# Main_Board_-_Double__Discrete.net
KiCad netlist of a schematic drawn in EAGLE
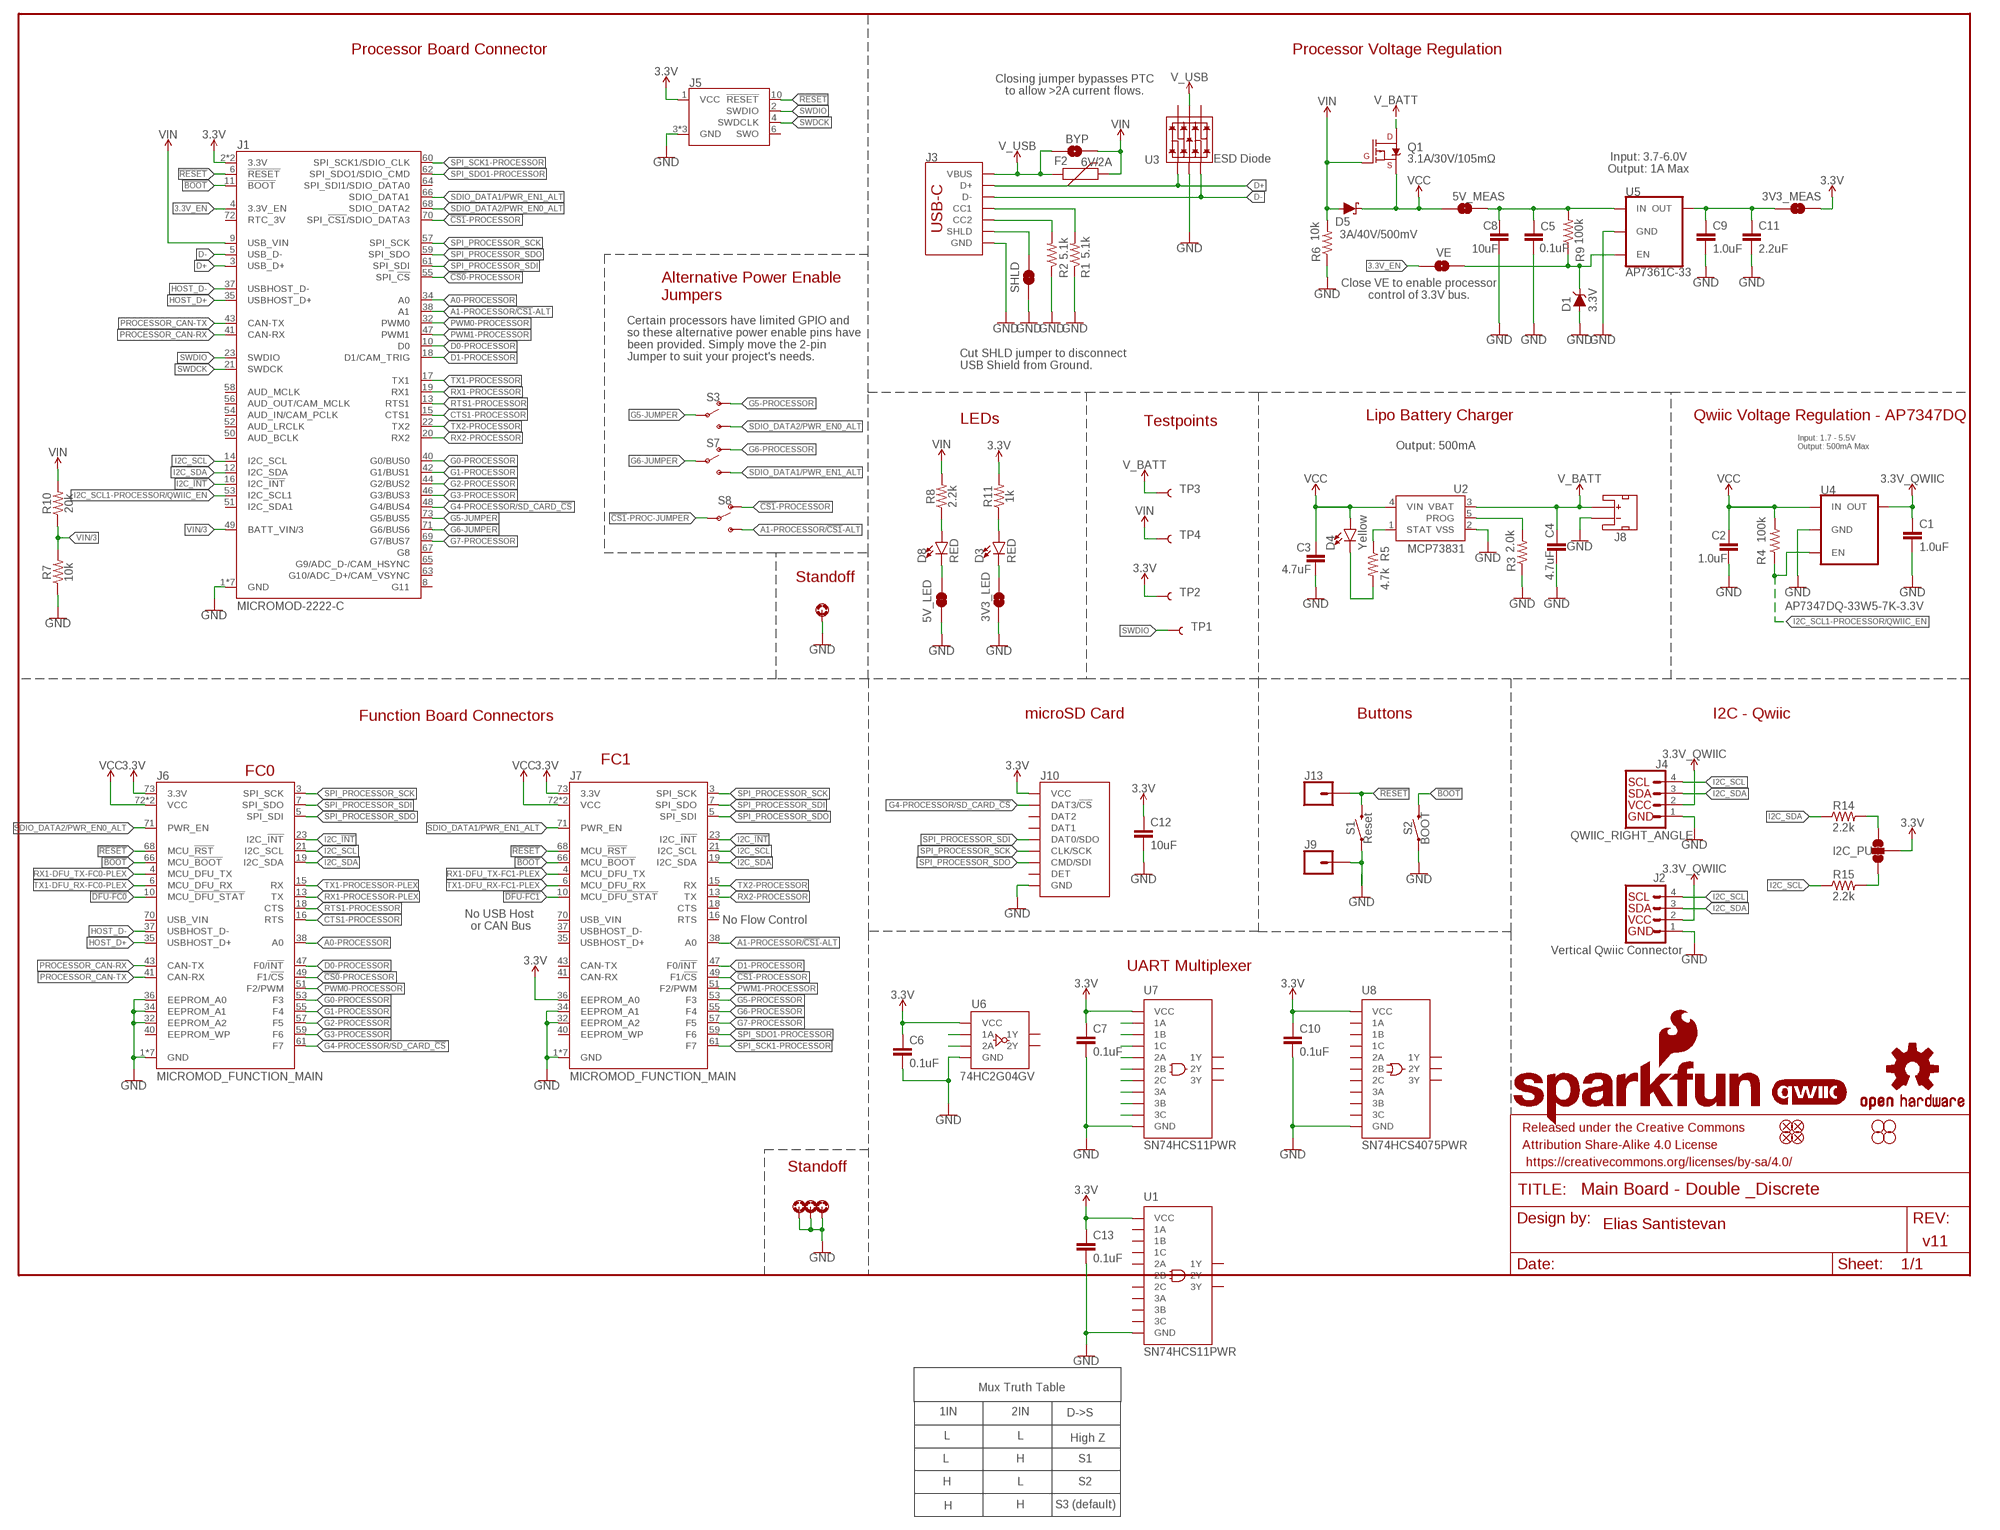
[diagram p0: schematic, sheet 1]

(export (version "E")
  (design (tool "Eeschema 10.0.6"))
  (components
    (comp (ref "3V3_LED")
      (value "JUMPER-SMT_2_NC_TRACE_SILK")
      (footprint "eagle-import:SMT-JUMPER_2_NC_TRACE_SILK")
      (libsource (lib "eagle-import") (part "JUMPER-SMT_2_NC_TRACE_SILK"))
    )
    (comp (ref "3V3_MEAS")
      (value "JUMPER-COMBO_2_NC_TRACE")
      (footprint "eagle-import:COMBO-JUMPER_2_NC_TRACE")
      (libsource (lib "eagle-import") (part "JUMPER-COMBO_2_NC_TRACE"))
    )
    (comp (ref "5V_LED")
      (value "JUMPER-SMT_2_NC_TRACE_SILK")
      (footprint "eagle-import:SMT-JUMPER_2_NC_TRACE_SILK")
      (libsource (lib "eagle-import") (part "JUMPER-SMT_2_NC_TRACE_SILK"))
    )
    (comp (ref "5V_MEAS")
      (value "JUMPER-COMBO_2_NC_TRACE")
      (footprint "eagle-import:COMBO-JUMPER_2_NC_TRACE")
      (libsource (lib "eagle-import") (part "JUMPER-COMBO_2_NC_TRACE"))
    )
    (comp (ref "BYP")
      (value "JUMPER-SMT_2_NO_SILK")
      (footprint "eagle-import:SMT-JUMPER_2_NO_SILK")
      (libsource (lib "eagle-import") (part "JUMPER-SMT_2_NO_SILK"))
    )
    (comp (ref "C1")
      (value "1.0uF")
      (footprint "eagle-import:0603")
      (libsource (lib "eagle-import") (part "1.0UF-0603-16V-10%"))
    )
    (comp (ref "C2")
      (value "1.0uF")
      (footprint "eagle-import:0603")
      (libsource (lib "eagle-import") (part "1.0UF-0603-16V-10%"))
    )
    (comp (ref "C3")
      (value "4.7uF")
      (footprint "eagle-import:0603")
      (libsource (lib "eagle-import") (part "4.7UF-0603-6.3V-(10%)"))
    )
    (comp (ref "C4")
      (value "4.7uF")
      (footprint "eagle-import:0603")
      (libsource (lib "eagle-import") (part "4.7UF-0603-35V-(20%)"))
    )
    (comp (ref "C5")
      (value "0.1uF")
      (footprint "eagle-import:0603")
      (libsource (lib "eagle-import") (part "0.1UF-0603-25V-(+80/-20%)"))
    )
    (comp (ref "C6")
      (value "0.1uF")
      (footprint "eagle-import:0603")
      (libsource (lib "eagle-import") (part "0.1UF-0603-25V-(+80/-20%)"))
    )
    (comp (ref "C7")
      (value "0.1uF")
      (footprint "eagle-import:0603")
      (libsource (lib "eagle-import") (part "0.1UF-0603-25V-(+80/-20%)"))
    )
    (comp (ref "C8")
      (value "10uF")
      (footprint "eagle-import:0805")
      (libsource (lib "eagle-import") (part "10UF-0805-10V-10%"))
    )
    (comp (ref "C9")
      (value "1.0uF")
      (footprint "eagle-import:0603")
      (libsource (lib "eagle-import") (part "1.0UF-0603-16V-10%"))
    )
    (comp (ref "C10")
      (value "0.1uF")
      (footprint "eagle-import:0603")
      (libsource (lib "eagle-import") (part "0.1UF-0603-25V-(+80/-20%)"))
    )
    (comp (ref "C11")
      (value "2.2uF")
      (footprint "eagle-import:0603")
      (libsource (lib "eagle-import") (part "2.2UF-0603-10V-20%"))
    )
    (comp (ref "C12")
      (value "10uF")
      (footprint "eagle-import:0603")
      (libsource (lib "eagle-import") (part "10UF-0603-6.3V-20%"))
    )
    (comp (ref "C13")
      (value "0.1uF")
      (footprint "eagle-import:0603")
      (libsource (lib "eagle-import") (part "0.1UF-0603-25V-(+80/-20%)"))
    )
    (comp (ref "D1")
      (value "3.3V")
      (footprint "eagle-import:SOD-323")
      (libsource (lib "eagle-import") (part "DIODE-ZENER-MM3Z3V3T1G"))
    )
    (comp (ref "D3")
      (value "RED")
      (footprint "eagle-import:LED-0603")
      (libsource (lib "eagle-import") (part "LED-RED0603"))
    )
    (comp (ref "D4")
      (value "Yellow")
      (footprint "eagle-import:LED-0603")
      (libsource (lib "eagle-import") (part "LED-YELLOW0603"))
    )
    (comp (ref "D5")
      (value "3A/40V/500mV")
      (footprint "eagle-import:SMA-DIODE")
      (libsource (lib "eagle-import") (part "DIODE-SCHOTTKY-B340A"))
    )
    (comp (ref "D8")
      (value "RED")
      (footprint "eagle-import:LED-0603")
      (libsource (lib "eagle-import") (part "LED-RED0603"))
    )
    (comp (ref "F2")
      (value "6V/2A")
      (footprint "eagle-import:1210")
      (libsource (lib "eagle-import") (part "PPTC_6V2A"))
    )
    (comp (ref "FD1")
      (value "FIDUCIAL1X2")
      (footprint "eagle-import:FIDUCIAL-1X2")
      (libsource (lib "eagle-import") (part "FIDUCIAL1X2"))
    )
    (comp (ref "FD2")
      (value "FIDUCIAL1X2")
      (footprint "eagle-import:FIDUCIAL-1X2")
      (libsource (lib "eagle-import") (part "FIDUCIAL1X2"))
    )
    (comp (ref "FD3")
      (value "FIDUCIAL1X2")
      (footprint "eagle-import:FIDUCIAL-1X2")
      (libsource (lib "eagle-import") (part "FIDUCIAL1X2"))
    )
    (comp (ref "FD4")
      (value "FIDUCIAL1X2")
      (footprint "eagle-import:FIDUCIAL-1X2")
      (libsource (lib "eagle-import") (part "FIDUCIAL1X2"))
    )
    (comp (ref "FRAME1")
      (value "FRAME-LEDGER")
      (footprint "eagle-import:CREATIVE_COMMONS")
      (libsource (lib "eagle-import") (part "FRAME-LEDGER"))
    )
    (comp (ref "H2")
      (value "STAND-OFF-REFLOW-M2.5_2.5MM_TALL")
      (footprint "eagle-import:STAND-OFF-REFLOW-M2.5")
      (libsource (lib "eagle-import") (part "STAND-OFF-REFLOW-M2.5_2.5MM_TALL"))
    )
    (comp (ref "H3")
      (value "STAND-OFF-REFLOW-M2.5_2.5MM_TALL")
      (footprint "eagle-import:STAND-OFF-REFLOW-M2.5")
      (libsource (lib "eagle-import") (part "STAND-OFF-REFLOW-M2.5_2.5MM_TALL"))
    )
    (comp (ref "H4")
      (value "STAND-OFF-REFLOW-M2.5_2.5MM_TALL")
      (footprint "eagle-import:STAND-OFF-REFLOW-M2.5")
      (libsource (lib "eagle-import") (part "STAND-OFF-REFLOW-M2.5_2.5MM_TALL"))
    )
    (comp (ref "H8")
      (value "STAND-OFF-REFLOW-M2.5_2.5MM_TALL")
      (footprint "eagle-import:STAND-OFF-REFLOW-M2.5")
      (libsource (lib "eagle-import") (part "STAND-OFF-REFLOW-M2.5_2.5MM_TALL"))
    )
    (comp (ref "H14")
      (value "STAND-OFFTIGHT")
      (footprint "eagle-import:STAND-OFF-TIGHT")
      (libsource (lib "eagle-import") (part "STAND-OFFTIGHT"))
    )
    (comp (ref "H15")
      (value "STAND-OFFTIGHT")
      (footprint "eagle-import:STAND-OFF-TIGHT")
      (libsource (lib "eagle-import") (part "STAND-OFFTIGHT"))
    )
    (comp (ref "H16")
      (value "STAND-OFFTIGHT")
      (footprint "eagle-import:STAND-OFF-TIGHT")
      (libsource (lib "eagle-import") (part "STAND-OFFTIGHT"))
    )
    (comp (ref "H17")
      (value "STAND-OFFTIGHT")
      (footprint "eagle-import:STAND-OFF-TIGHT")
      (libsource (lib "eagle-import") (part "STAND-OFFTIGHT"))
    )
    (comp (ref "I2C_PU")
      (value "JUMPER-SMT_3_2-NC_TRACE_SILK")
      (footprint "eagle-import:SMT-JUMPER_3_2-NC_TRACE_SILK")
      (libsource (lib "eagle-import") (part "JUMPER-SMT_3_2-NC_TRACE_SILK"))
    )
    (comp (ref "J1")
      (value "MICROMOD-2222-C")
      (footprint "eagle-import:M.2-CONNECTOR-E")
      (libsource (lib "eagle-import") (part "MICROMOD-2222-C"))
    )
    (comp (ref "J2")
      (value "Vertical Qwiic Connector")
      (footprint "eagle-import:JST04_1MM_VERT")
      (libsource (lib "eagle-import") (part "QWIIC_CONNECTOR"))
    )
    (comp (ref "J3")
      (value "USB_C_2-LAYER_PADS")
      (footprint "eagle-import:USB-C-16P-2LAYER-PADS")
      (libsource (lib "eagle-import") (part "USB_C_2-LAYER_PADS"))
    )
    (comp (ref "J4")
      (value "QWIIC_RIGHT_ANGLE")
      (footprint "eagle-import:JST04_1MM_RA")
      (libsource (lib "eagle-import") (part "QWIIC_CONNECTORJS-1MM"))
    )
    (comp (ref "J5")
      (value "CORTEX_JTAG_DEBUG_MINIMUM_PTH")
      (footprint "eagle-import:2X5-PTH-1.27MM")
      (libsource (lib "eagle-import") (part "CORTEX_JTAG_DEBUG_MINIMUM_PTH"))
    )
    (comp (ref "J6")
      (value "MICROMOD_FUNCTION_MAIN")
      (footprint "eagle-import:M.2-CONNECTOR-E-FUNCTION-STANDARD")
      (libsource (lib "eagle-import") (part "MICROMOD_FUNCTION_MAIN"))
    )
    (comp (ref "J7")
      (value "MICROMOD_FUNCTION_MAIN")
      (footprint "eagle-import:M.2-CONNECTOR-E-FUNCTION-STANDARD")
      (libsource (lib "eagle-import") (part "MICROMOD_FUNCTION_MAIN"))
    )
    (comp (ref "J8")
      (value "JST_2MM_MALE")
      (footprint "eagle-import:JST-2-SMD")
      (libsource (lib "eagle-import") (part "JST_2MM_MALE"))
    )
    (comp (ref "J9")
      (value "CONN_01PTH_NO_SILK_YES_STOP")
      (footprint "eagle-import:1X01_NO_SILK")
      (libsource (lib "eagle-import") (part "CONN_01PTH_NO_SILK_YES_STOP"))
    )
    (comp (ref "J10")
      (value "MICRO-SD-PUSH-PUSH-EXT-PIN")
      (footprint "eagle-import:MICROSD-EXTERNALPIN")
      (libsource (lib "eagle-import") (part "MICRO-SD-PUSH-PUSH-EXT-PIN"))
    )
    (comp (ref "J13")
      (value "CONN_01PTH_NO_SILK_YES_STOP")
      (footprint "eagle-import:1X01_NO_SILK")
      (libsource (lib "eagle-import") (part "CONN_01PTH_NO_SILK_YES_STOP"))
    )
    (comp (ref "LOGO1")
      (value "QWIIC_LOGO_8MM")
      (footprint "eagle-import:QWIIC_8MM")
      (libsource (lib "eagle-import") (part "QWIIC_LOGO_8MM"))
    )
    (comp (ref "LOGO2")
      (value "SFE_LOGO_NAME_FLAME.3_INCH")
      (footprint "eagle-import:SFE_LOGO_NAME_FLAME_.3")
      (libsource (lib "eagle-import") (part "SFE_LOGO_NAME_FLAME.3_INCH"))
    )
    (comp (ref "LOGO3")
      (value "OSHW-LOGOL")
      (footprint "eagle-import:OSHW-LOGO-L")
      (libsource (lib "eagle-import") (part "OSHW-LOGOL"))
    )
    (comp (ref "Q1")
      (value "3.1A/30V/105mΩ")
      (footprint "eagle-import:SOT23-3")
      (libsource (lib "eagle-import") (part "MOSFET_PCH-DMG2307L"))
    )
    (comp (ref "R1")
      (value "5.1k")
      (footprint "eagle-import:0603")
      (libsource (lib "eagle-import") (part "5.1KOHM5.1KOHM-0603-1/10W-1%"))
    )
    (comp (ref "R2")
      (value "5.1k")
      (footprint "eagle-import:0603")
      (libsource (lib "eagle-import") (part "5.1KOHM5.1KOHM-0603-1/10W-1%"))
    )
    (comp (ref "R3")
      (value "2.0k")
      (footprint "eagle-import:0603")
      (libsource (lib "eagle-import") (part "2.0KOHM-0603-1/10W-5%"))
    )
    (comp (ref "R4")
      (value "100k")
      (footprint "eagle-import:0603")
      (libsource (lib "eagle-import") (part "100KOHM-0603-1/10W-1%"))
    )
    (comp (ref "R5")
      (value "4.7k")
      (footprint "eagle-import:0603")
      (libsource (lib "eagle-import") (part "4.7KOHM-0603-1/10W-1%"))
    )
    (comp (ref "R6")
      (value "10k")
      (footprint "eagle-import:0603")
      (libsource (lib "eagle-import") (part "10KOHM-0603-1/10W-1%"))
    )
    (comp (ref "R7")
      (value "10k")
      (footprint "eagle-import:0603")
      (libsource (lib "eagle-import") (part "10KOHM-0603-1/10W-1%"))
    )
    (comp (ref "R8")
      (value "2.2k")
      (footprint "eagle-import:0603")
      (libsource (lib "eagle-import") (part "2.2KOHM-0603-1/10W-1%"))
    )
    (comp (ref "R9")
      (value "100k")
      (footprint "eagle-import:0603")
      (libsource (lib "eagle-import") (part "100KOHM-0603-1/10W-1%"))
    )
    (comp (ref "R10")
      (value "20k")
      (footprint "eagle-import:0603")
      (libsource (lib "eagle-import") (part "20KOHM-0603-1/10W-1%"))
    )
    (comp (ref "R11")
      (value "1k")
      (footprint "eagle-import:0603")
      (libsource (lib "eagle-import") (part "1KOHM-0603-1/10W-1%"))
    )
    (comp (ref "R14")
      (value "2.2k")
      (footprint "eagle-import:0603")
      (libsource (lib "eagle-import") (part "2.2KOHM-0603-1/10W-1%"))
    )
    (comp (ref "R15")
      (value "2.2k")
      (footprint "eagle-import:0603")
      (libsource (lib "eagle-import") (part "2.2KOHM-0603-1/10W-1%"))
    )
    (comp (ref "S1")
      (value "Reset")
      (footprint "eagle-import:TACTILE_SWITCH_SMD_5.2MM")
      (libsource (lib "eagle-import") (part "MOMENTARY-SWITCH-SPST-SMD-5.2-TALL-REDUNDANT"))
    )
    (comp (ref "S2")
      (value "BOOT")
      (footprint "eagle-import:TACTILE_SWITCH_SMD_5.2MM")
      (libsource (lib "eagle-import") (part "MOMENTARY-SWITCH-SPST-SMD-5.2-TALL-REDUNDANT"))
    )
    (comp (ref "S3")
      (value "SWITCH-SPDT-SMD-RIGHT-ANGLE")
      (footprint "eagle-import:SWITCH_SPST_SMD_A")
      (libsource (lib "eagle-import") (part "SWITCH-SPDT-SMD-RIGHT-ANGLE"))
    )
    (comp (ref "S7")
      (value "SWITCH-SPDT-SMD-RIGHT-ANGLE")
      (footprint "eagle-import:SWITCH_SPST_SMD_A")
      (libsource (lib "eagle-import") (part "SWITCH-SPDT-SMD-RIGHT-ANGLE"))
    )
    (comp (ref "S8")
      (value "SWITCH-SPDT-SMD-RIGHT-ANGLE")
      (footprint "eagle-import:SWITCH_SPST_SMD_A")
      (libsource (lib "eagle-import") (part "SWITCH-SPDT-SMD-RIGHT-ANGLE"))
    )
    (comp (ref "SHLD")
      (value "JUMPER-SMT_2_NC_TRACE_SILK")
      (footprint "eagle-import:SMT-JUMPER_2_NC_TRACE_SILK")
      (libsource (lib "eagle-import") (part "JUMPER-SMT_2_NC_TRACE_SILK"))
    )
    (comp (ref "TP1")
      (value "TEST-POINT3X5")
      (footprint "eagle-import:PAD.03X.05")
      (libsource (lib "eagle-import") (part "TEST-POINT3X5"))
    )
    (comp (ref "TP2")
      (value "TEST-POINT3X5")
      (footprint "eagle-import:PAD.03X.05")
      (libsource (lib "eagle-import") (part "TEST-POINT3X5"))
    )
    (comp (ref "TP3")
      (value "TEST-POINT3X5")
      (footprint "eagle-import:PAD.03X.05")
      (libsource (lib "eagle-import") (part "TEST-POINT3X5"))
    )
    (comp (ref "TP4")
      (value "TEST-POINT3X5")
      (footprint "eagle-import:PAD.03X.05")
      (libsource (lib "eagle-import") (part "TEST-POINT3X5"))
    )
    (comp (ref "U1")
      (value "SN74HCS11PWR")
      (footprint "eagle-import:TSSOP14")
      (libsource (lib "eagle-import") (part "SN74HCS11PWR"))
    )
    (comp (ref "U2")
      (value "MCP73831")
      (footprint "eagle-import:SOT23-5")
      (libsource (lib "eagle-import") (part "MCP73831"))
    )
    (comp (ref "U3")
      (value "ESD Diode")
      (footprint "eagle-import:SOT-23-6")
      (libsource (lib "eagle-import") (part "TVS_DIODE_ARRAYSMD"))
    )
    (comp (ref "U4")
      (value "AP7347DQ-33W5-7K-3.3V")
      (footprint "eagle-import:SOT25")
      (libsource (lib "eagle-import") (part "AP7347DQ-33W5-7K-3.3V"))
    )
    (comp (ref "U5")
      (value "AP7361C-33")
      (footprint "eagle-import:UDFN-8")
      (libsource (lib "eagle-import") (part "AP7361C-33FGEUDFN-8"))
    )
    (comp (ref "U6")
      (value "74HC2G04GV")
      (footprint "eagle-import:TSSOP6")
      (libsource (lib "eagle-import") (part "74HC2G04GV"))
    )
    (comp (ref "U7")
      (value "SN74HCS11PWR")
      (footprint "eagle-import:TSSOP14")
      (libsource (lib "eagle-import") (part "SN74HCS11PWR"))
    )
    (comp (ref "U8")
      (value "SN74HCS4075PWR")
      (footprint "eagle-import:TSSOP14")
      (libsource (lib "eagle-import") (part "SN74HCS4075PWR"))
    )
    (comp (ref "VE")
      (value "JUMPER-SMT_2_NO_SILK")
      (footprint "eagle-import:SMT-JUMPER_2_NO_SILK")
      (libsource (lib "eagle-import") (part "JUMPER-SMT_2_NO_SILK"))
    )
  )
  (nets
    (net (code "1") (name "/A1-PROCESSOR{slash}~{CS1}-ALT") (class "Default")
      (node (ref "J1") (pin "38") (pinfunction "A1_38") (pintype "bidirectional"))
      (node (ref "J7") (pin "38") (pinfunction "A0_38") (pintype "bidirectional"))
      (node (ref "S8") (pin "3") (pinfunction "S_3") (pintype "passive"))
    )
    (net (code "2") (name "/G4-PROCESSOR{slash}SD_CARD_~{CS}") (class "Default")
      (node (ref "J1") (pin "48") (pinfunction "G4/BUS4_48") (pintype "bidirectional"))
      (node (ref "J10") (pin "2") (pinfunction "DAT3/~{CS}_2") (pintype "bidirectional"))
      (node (ref "J6") (pin "61") (pinfunction "F7_61") (pintype "bidirectional"))
    )
    (net (code "3") (name "/I2C_~{INT}") (class "Default")
      (node (ref "J1") (pin "16") (pinfunction "I2C_~{INT}_16") (pintype "bidirectional"))
      (node (ref "J6") (pin "23") (pinfunction "I2C_~{INT}_23") (pintype "bidirectional"))
      (node (ref "J7") (pin "23") (pinfunction "I2C_~{INT}_23") (pintype "bidirectional"))
    )
    (net (code "4") (name "/~{BOOT}") (class "Default")
      (node (ref "J1") (pin "11") (pinfunction "~{BOOT}_11") (pintype "bidirectional"))
      (node (ref "J6") (pin "66") (pinfunction "MCU_~{BOOT}_66") (pintype "bidirectional"))
      (node (ref "J7") (pin "66") (pinfunction "MCU_~{BOOT}_66") (pintype "bidirectional"))
      (node (ref "S2") (pin "3") (pinfunction "2_3") (pintype "passive"))
      (node (ref "S2") (pin "4") (pinfunction "2_4") (pintype "passive"))
    )
    (net (code "5") (name "/~{CS0}-PROCESSOR") (class "Default")
      (node (ref "J1") (pin "55") (pinfunction "SPI_~{CS}_55") (pintype "bidirectional"))
      (node (ref "J6") (pin "49") (pinfunction "F1/~{CS}_49") (pintype "bidirectional"))
    )
    (net (code "6") (name "/~{CS1}-PROC-JUMPER") (class "Default")
      (node (ref "S8") (pin "2") (pinfunction "P_2") (pintype "passive"))
    )
    (net (code "7") (name "/~{CS1}-PROCESSOR") (class "Default")
      (node (ref "J1") (pin "70") (pinfunction "SPI_~{CS1}/SDIO_DATA3_70") (pintype "bidirectional"))
      (node (ref "J7") (pin "49") (pinfunction "F1/~{CS}_49") (pintype "bidirectional"))
      (node (ref "S8") (pin "1") (pinfunction "O_1") (pintype "passive"))
    )
    (net (code "8") (name "/~{DFU-FC0}") (class "Default")
      (node (ref "J6") (pin "10") (pinfunction "MCU_~{DFU_STAT}_10") (pintype "bidirectional"))
    )
    (net (code "9") (name "/~{DFU-FC1}") (class "Default")
      (node (ref "J7") (pin "10") (pinfunction "MCU_~{DFU_STAT}_10") (pintype "bidirectional"))
    )
    (net (code "10") (name "/~{RESET}") (class "Default")
      (node (ref "J1") (pin "6") (pinfunction "~{RESET}_6") (pintype "bidirectional"))
      (node (ref "J13") (pin "1") (pinfunction "1_1") (pintype "passive"))
      (node (ref "J5") (pin "10") (pinfunction "~{RESET}_10") (pintype "bidirectional"))
      (node (ref "J6") (pin "68") (pinfunction "MCU_~{RST}_68") (pintype "bidirectional"))
      (node (ref "J7") (pin "68") (pinfunction "MCU_~{RST}_68") (pintype "bidirectional"))
      (node (ref "S1") (pin "3") (pinfunction "2_3") (pintype "passive"))
      (node (ref "S1") (pin "4") (pinfunction "2_4") (pintype "passive"))
    )
    (net (code "11") (name "3.3V") (class "Default")
      (node (ref "3V3_MEAS") (pin "2") (pinfunction "2_2") (pintype "passive"))
      (node (ref "3V3_MEAS") (pin "4") (pinfunction "2_4") (pintype "passive"))
      (node (ref "C10") (pin "1") (pinfunction "1_1") (pintype "passive"))
      (node (ref "C12") (pin "1") (pinfunction "1_1") (pintype "passive"))
      (node (ref "C13") (pin "1") (pinfunction "1_1") (pintype "passive"))
      (node (ref "C6") (pin "1") (pinfunction "1_1") (pintype "passive"))
      (node (ref "C7") (pin "1") (pinfunction "1_1") (pintype "passive"))
      (node (ref "I2C_PU") (pin "2") (pinfunction "2_2") (pintype "passive"))
      (node (ref "J1") (pin "2") (pinfunction "3.3V_2") (pintype "bidirectional"))
      (node (ref "J1") (pin "74") (pinfunction "3.3V_74") (pintype "bidirectional"))
      (node (ref "J10") (pin "4") (pinfunction "VCC_4") (pintype "bidirectional"))
      (node (ref "J5") (pin "1") (pinfunction "VCC_1") (pintype "bidirectional"))
      (node (ref "J6") (pin "73") (pinfunction "3.3V_73") (pintype "bidirectional"))
      (node (ref "J7") (pin "36") (pinfunction "EEPROM_A0_36") (pintype "bidirectional"))
      (node (ref "J7") (pin "73") (pinfunction "3.3V_73") (pintype "bidirectional"))
      (node (ref "R11") (pin "2") (pinfunction "2_2") (pintype "passive"))
      (node (ref "TP2") (pin "1") (pinfunction "1_1") (pintype "bidirectional"))
      (node (ref "U1") (pin "P14") (pinfunction "VCC_P14") (pintype "power_in"))
      (node (ref "U6") (pin "P5") (pinfunction "VCC_P5") (pintype "power_in"))
      (node (ref "U7") (pin "P14") (pinfunction "VCC_P14") (pintype "power_in"))
      (node (ref "U8") (pin "P14") (pinfunction "VCC_P14") (pintype "power_in"))
    )
    (net (code "12") (name "3.3V_EN") (class "Default")
      (node (ref "J1") (pin "4") (pinfunction "3.3V_EN_4") (pintype "bidirectional"))
      (node (ref "VE") (pin "1") (pinfunction "1_1") (pintype "passive"))
    )
    (net (code "13") (name "3.3V_QWIIC") (class "Default")
      (node (ref "C1") (pin "1") (pinfunction "1_1") (pintype "passive"))
      (node (ref "J2") (pin "2") (pinfunction "2_2") (pintype "power_in"))
      (node (ref "J4") (pin "2") (pinfunction "2_2") (pintype "power_in"))
      (node (ref "U4") (pin "5") (pinfunction "OUT_5") (pintype "passive"))
    )
    (net (code "14") (name "A0-PROCESSOR") (class "Default")
      (node (ref "J1") (pin "34") (pinfunction "A0_34") (pintype "bidirectional"))
      (node (ref "J6") (pin "38") (pinfunction "A0_38") (pintype "bidirectional"))
    )
    (net (code "15") (name "CTS1-PROCESSOR") (class "Default")
      (node (ref "J1") (pin "15") (pinfunction "CTS1_15") (pintype "bidirectional"))
      (node (ref "J6") (pin "16") (pinfunction "RTS_16") (pintype "bidirectional"))
    )
    (net (code "16") (name "D+") (class "Default")
      (node (ref "J1") (pin "3") (pinfunction "USB_D+_3") (pintype "bidirectional"))
      (node (ref "J3") (pin "A6") (pinfunction "D+_A6") (pintype "bidirectional"))
      (node (ref "J3") (pin "B6") (pinfunction "D+_B6") (pintype "bidirectional"))
      (node (ref "U3") (pin "1") (pinfunction "IO1_1") (pintype "bidirectional"))
    )
    (net (code "17") (name "D-") (class "Default")
      (node (ref "J1") (pin "5") (pinfunction "USB_D-_5") (pintype "bidirectional"))
      (node (ref "J3") (pin "A7") (pinfunction "D-_A7") (pintype "bidirectional"))
      (node (ref "J3") (pin "B7") (pinfunction "D-_B7") (pintype "bidirectional"))
      (node (ref "U3") (pin "3") (pinfunction "IO2_3") (pintype "bidirectional"))
    )
    (net (code "18") (name "D0-PROCESSOR") (class "Default")
      (node (ref "J1") (pin "10") (pinfunction "D0_10") (pintype "bidirectional"))
      (node (ref "J6") (pin "47") (pinfunction "F0/~{INT}_47") (pintype "bidirectional"))
    )
    (net (code "19") (name "D1-PROCESSOR") (class "Default")
      (node (ref "J1") (pin "18") (pinfunction "D1/CAM_TRIG_18") (pintype "bidirectional"))
      (node (ref "J7") (pin "47") (pinfunction "F0/~{INT}_47") (pintype "bidirectional"))
    )
    (net (code "20") (name "G0-PROCESSOR") (class "Default")
      (node (ref "J1") (pin "40") (pinfunction "G0/BUS0_40") (pintype "bidirectional"))
      (node (ref "J6") (pin "53") (pinfunction "F3_53") (pintype "bidirectional"))
    )
    (net (code "21") (name "G1-PROCESSOR") (class "Default")
      (node (ref "J1") (pin "42") (pinfunction "G1/BUS1_42") (pintype "bidirectional"))
      (node (ref "J6") (pin "55") (pinfunction "F4_55") (pintype "bidirectional"))
    )
    (net (code "22") (name "G2-PROCESSOR") (class "Default")
      (node (ref "J1") (pin "44") (pinfunction "G2/BUS2_44") (pintype "bidirectional"))
      (node (ref "J6") (pin "57") (pinfunction "F5_57") (pintype "bidirectional"))
    )
    (net (code "23") (name "G3-PROCESSOR") (class "Default")
      (node (ref "J1") (pin "46") (pinfunction "G3/BUS3_46") (pintype "bidirectional"))
      (node (ref "J6") (pin "59") (pinfunction "F6_59") (pintype "bidirectional"))
    )
    (net (code "24") (name "G5-JUMPER") (class "Default")
      (node (ref "J1") (pin "73") (pinfunction "G5/BUS5_73") (pintype "bidirectional"))
      (node (ref "S3") (pin "2") (pinfunction "P_2") (pintype "passive"))
    )
    (net (code "25") (name "G5-PROCESSOR") (class "Default")
      (node (ref "J7") (pin "53") (pinfunction "F3_53") (pintype "bidirectional"))
      (node (ref "S3") (pin "1") (pinfunction "O_1") (pintype "passive"))
    )
    (net (code "26") (name "G6-JUMPER") (class "Default")
      (node (ref "J1") (pin "71") (pinfunction "G6/BUS6_71") (pintype "bidirectional"))
      (node (ref "S7") (pin "2") (pinfunction "P_2") (pintype "passive"))
    )
    (net (code "27") (name "G6-PROCESSOR") (class "Default")
      (node (ref "J7") (pin "55") (pinfunction "F4_55") (pintype "bidirectional"))
      (node (ref "S7") (pin "1") (pinfunction "O_1") (pintype "passive"))
    )
    (net (code "28") (name "G7-PROCESSOR") (class "Default")
      (node (ref "J1") (pin "69") (pinfunction "G7/BUS7_69") (pintype "bidirectional"))
      (node (ref "J7") (pin "57") (pinfunction "F5_57") (pintype "bidirectional"))
    )
    (net (code "29") (name "GND") (class "Default")
      (node (ref "3V3_LED") (pin "1") (pinfunction "1_1") (pintype "passive"))
      (node (ref "5V_LED") (pin "1") (pinfunction "1_1") (pintype "passive"))
      (node (ref "C1") (pin "2") (pinfunction "2_2") (pintype "passive"))
      (node (ref "C10") (pin "2") (pinfunction "2_2") (pintype "passive"))
      (node (ref "C11") (pin "2") (pinfunction "2_2") (pintype "passive"))
      (node (ref "C12") (pin "2") (pinfunction "2_2") (pintype "passive"))
      (node (ref "C13") (pin "2") (pinfunction "2_2") (pintype "passive"))
      (node (ref "C2") (pin "2") (pinfunction "2_2") (pintype "passive"))
      (node (ref "C3") (pin "2") (pinfunction "2_2") (pintype "passive"))
      (node (ref "C4") (pin "2") (pinfunction "2_2") (pintype "passive"))
      (node (ref "C5") (pin "2") (pinfunction "2_2") (pintype "passive"))
      (node (ref "C6") (pin "2") (pinfunction "2_2") (pintype "passive"))
      (node (ref "C7") (pin "2") (pinfunction "2_2") (pintype "passive"))
      (node (ref "C8") (pin "2") (pinfunction "2_2") (pintype "passive"))
      (node (ref "C9") (pin "2") (pinfunction "2_2") (pintype "passive"))
      (node (ref "D1") (pin "A") (pinfunction "A_A") (pintype "passive"))
      (node (ref "H2") (pin "1") (pinfunction "1_1") (pintype "bidirectional"))
      (node (ref "H3") (pin "1") (pinfunction "1_1") (pintype "bidirectional"))
      (node (ref "H4") (pin "1") (pinfunction "1_1") (pintype "bidirectional"))
      (node (ref "H8") (pin "1") (pinfunction "1_1") (pintype "bidirectional"))
      (node (ref "J1") (pin "1") (pinfunction "GND_1") (pintype "bidirectional"))
      (node (ref "J1") (pin "33") (pinfunction "GND_33") (pintype "bidirectional"))
      (node (ref "J1") (pin "36") (pinfunction "GND_36") (pintype "bidirectional"))
      (node (ref "J1") (pin "39") (pinfunction "GND_39") (pintype "bidirectional"))
      (node (ref "J1") (pin "45") (pinfunction "GND_45") (pintype "bidirectional"))
      (node (ref "J1") (pin "7") (pinfunction "GND_7") (pintype "bidirectional"))
      (node (ref "J1") (pin "75") (pinfunction "GND_75") (pintype "bidirectional"))
      (node (ref "J10") (pin "10") (pinfunction "GND_10") (pintype "bidirectional"))
      (node (ref "J10") (pin "11") (pinfunction "GND_11") (pintype "bidirectional"))
      (node (ref "J10") (pin "12") (pinfunction "GND_12") (pintype "bidirectional"))
      (node (ref "J10") (pin "13") (pinfunction "GND_13") (pintype "bidirectional"))
      (node (ref "J10") (pin "6") (pinfunction "GND_6") (pintype "bidirectional"))
      (node (ref "J2") (pin "1") (pinfunction "1_1") (pintype "power_in"))
      (node (ref "J3") (pin "GND") (pinfunction "GND_GND") (pintype "bidirectional"))
      (node (ref "J3") (pin "GND2") (pinfunction "GND_GND2") (pintype "bidirectional"))
      (node (ref "J4") (pin "1") (pinfunction "1_1") (pintype "power_in"))
      (node (ref "J5") (pin "3") (pinfunction "GND_3") (pintype "bidirectional"))
      (node (ref "J5") (pin "5") (pinfunction "GND_5") (pintype "bidirectional"))
      (node (ref "J5") (pin "9") (pinfunction "GND_9") (pintype "bidirectional"))
      (node (ref "J6") (pin "1") (pinfunction "GND_1") (pintype "bidirectional"))
      (node (ref "J6") (pin "2") (pinfunction "GND_2") (pintype "bidirectional"))
      (node (ref "J6") (pin "32") (pinfunction "EEPROM_A2_32") (pintype "bidirectional"))
      (node (ref "J6") (pin "33") (pinfunction "GND_33") (pintype "bidirectional"))
      (node (ref "J6") (pin "34") (pinfunction "EEPROM_A1_34") (pintype "bidirectional"))
      (node (ref "J6") (pin "36") (pinfunction "EEPROM_A0_36") (pintype "bidirectional"))
      (node (ref "J6") (pin "39") (pinfunction "GND_39") (pintype "bidirectional"))
      (node (ref "J6") (pin "45") (pinfunction "GND_45") (pintype "bidirectional"))
      (node (ref "J6") (pin "75") (pinfunction "GND_75") (pintype "bidirectional"))
      (node (ref "J6") (pin "8") (pinfunction "GND_8") (pintype "bidirectional"))
      (node (ref "J7") (pin "1") (pinfunction "GND_1") (pintype "bidirectional"))
      (node (ref "J7") (pin "2") (pinfunction "GND_2") (pintype "bidirectional"))
      (node (ref "J7") (pin "32") (pinfunction "EEPROM_A2_32") (pintype "bidirectional"))
      (node (ref "J7") (pin "33") (pinfunction "GND_33") (pintype "bidirectional"))
      (node (ref "J7") (pin "34") (pinfunction "EEPROM_A1_34") (pintype "bidirectional"))
      (node (ref "J7") (pin "39") (pinfunction "GND_39") (pintype "bidirectional"))
      (node (ref "J7") (pin "45") (pinfunction "GND_45") (pintype "bidirectional"))
      (node (ref "J7") (pin "75") (pinfunction "GND_75") (pintype "bidirectional"))
      (node (ref "J7") (pin "8") (pinfunction "GND_8") (pintype "bidirectional"))
      (node (ref "J8") (pin "1") (pinfunction "-_1") (pintype "bidirectional"))
      (node (ref "J9") (pin "1") (pinfunction "1_1") (pintype "passive"))
      (node (ref "R1") (pin "1") (pinfunction "1_1") (pintype "passive"))
      (node (ref "R2") (pin "1") (pinfunction "1_1") (pintype "passive"))
      (node (ref "R3") (pin "1") (pinfunction "1_1") (pintype "passive"))
      (node (ref "R6") (pin "1") (pinfunction "1_1") (pintype "passive"))
      (node (ref "R7") (pin "1") (pinfunction "1_1") (pintype "passive"))
      (node (ref "S1") (pin "1") (pinfunction "1_1") (pintype "passive"))
      (node (ref "S1") (pin "2") (pinfunction "1_2") (pintype "passive"))
      (node (ref "S2") (pin "1") (pinfunction "1_1") (pintype "passive"))
      (node (ref "S2") (pin "2") (pinfunction "1_2") (pintype "passive"))
      (node (ref "SHLD") (pin "1") (pinfunction "1_1") (pintype "passive"))
      (node (ref "U1") (pin "P7") (pinfunction "GND_P7") (pintype "power_in"))
      (node (ref "U2") (pin "2") (pinfunction "VSS_2") (pintype "power_in"))
      (node (ref "U3") (pin "2") (pinfunction "VSS_2") (pintype "bidirectional"))
      (node (ref "U4") (pin "2") (pinfunction "GND_2") (pintype "input"))
      (node (ref "U5") (pin "4") (pinfunction "GND_4") (pintype "input"))
      (node (ref "U5") (pin "EP") (pinfunction "GND_EP") (pintype "input"))
      (node (ref "U6") (pin "P2") (pinfunction "GND_P2") (pintype "power_in"))
      (node (ref "U7") (pin "P7") (pinfunction "GND_P7") (pintype "power_in"))
      (node (ref "U8") (pin "P7") (pinfunction "GND_P7") (pintype "power_in"))
    )
    (net (code "30") (name "HOST_D+") (class "Default")
      (node (ref "J1") (pin "35") (pinfunction "USBHOST_D+_35") (pintype "bidirectional"))
      (node (ref "J6") (pin "35") (pinfunction "USBHOST_D+_35") (pintype "bidirectional"))
    )
    (net (code "31") (name "HOST_D-") (class "Default")
      (node (ref "J1") (pin "37") (pinfunction "USBHOST_D-_37") (pintype "bidirectional"))
      (node (ref "J6") (pin "37") (pinfunction "USBHOST_D-_37") (pintype "bidirectional"))
    )
    (net (code "32") (name "I2C_SCL") (class "Default")
      (node (ref "J1") (pin "14") (pinfunction "I2C_SCL_14") (pintype "bidirectional"))
      (node (ref "J2") (pin "4") (pinfunction "4_4") (pintype "passive"))
      (node (ref "J4") (pin "4") (pinfunction "4_4") (pintype "passive"))
      (node (ref "J6") (pin "21") (pinfunction "I2C_SCL_21") (pintype "bidirectional"))
      (node (ref "J7") (pin "21") (pinfunction "I2C_SCL_21") (pintype "bidirectional"))
      (node (ref "R15") (pin "1") (pinfunction "1_1") (pintype "passive"))
    )
    (net (code "33") (name "I2C_SCL1-PROCESSOR{slash}QWIIC_EN") (class "Default")
      (node (ref "J1") (pin "53") (pinfunction "I2C_SCL1_53") (pintype "bidirectional"))
      (node (ref "R4") (pin "1") (pinfunction "1_1") (pintype "passive"))
      (node (ref "U4") (pin "3") (pinfunction "EN_3") (pintype "input"))
    )
    (net (code "34") (name "I2C_SDA") (class "Default")
      (node (ref "J1") (pin "12") (pinfunction "I2C_SDA_12") (pintype "bidirectional"))
      (node (ref "J2") (pin "3") (pinfunction "3_3") (pintype "passive"))
      (node (ref "J4") (pin "3") (pinfunction "3_3") (pintype "passive"))
      (node (ref "J6") (pin "19") (pinfunction "I2C_SDA_19") (pintype "bidirectional"))
      (node (ref "J7") (pin "19") (pinfunction "I2C_SDA_19") (pintype "bidirectional"))
      (node (ref "R14") (pin "1") (pinfunction "1_1") (pintype "passive"))
    )
    (net (code "35") (name "Net-(3V3_LED-Pad2)") (class "Default")
      (node (ref "3V3_LED") (pin "2") (pinfunction "2_2") (pintype "passive"))
      (node (ref "D3") (pin "C") (pinfunction "C_C") (pintype "passive"))
    )
    (net (code "36") (name "Net-(5V_LED-Pad2)") (class "Default")
      (node (ref "5V_LED") (pin "2") (pinfunction "2_2") (pintype "passive"))
      (node (ref "D8") (pin "C") (pinfunction "C_C") (pintype "passive"))
    )
    (net (code "37") (name "Net-(D3-PadA)") (class "Default")
      (node (ref "D3") (pin "A") (pinfunction "A_A") (pintype "passive"))
      (node (ref "R11") (pin "1") (pinfunction "1_1") (pintype "passive"))
    )
    (net (code "38") (name "Net-(D4-PadC)") (class "Default")
      (node (ref "D4") (pin "C") (pinfunction "C_C") (pintype "passive"))
      (node (ref "R5") (pin "2") (pinfunction "2_2") (pintype "passive"))
    )
    (net (code "39") (name "Net-(D8-PadA)") (class "Default")
      (node (ref "D8") (pin "A") (pinfunction "A_A") (pintype "passive"))
      (node (ref "R8") (pin "1") (pinfunction "1_1") (pintype "passive"))
    )
    (net (code "40") (name "Net-(I2C_PU-Pad1)") (class "Default")
      (node (ref "I2C_PU") (pin "1") (pinfunction "1_1") (pintype "passive"))
      (node (ref "R15") (pin "2") (pinfunction "2_2") (pintype "passive"))
    )
    (net (code "41") (name "Net-(I2C_PU-Pad3)") (class "Default")
      (node (ref "I2C_PU") (pin "3") (pinfunction "3_3") (pintype "passive"))
      (node (ref "R14") (pin "2") (pinfunction "2_2") (pintype "passive"))
    )
    (net (code "42") (name "Net-(J3-CC1)") (class "Default")
      (node (ref "J3") (pin "A5") (pinfunction "CC1_A5") (pintype "bidirectional"))
      (node (ref "R1") (pin "2") (pinfunction "2_2") (pintype "passive"))
    )
    (net (code "43") (name "Net-(J3-CC2)") (class "Default")
      (node (ref "J3") (pin "B5") (pinfunction "CC2_B5") (pintype "bidirectional"))
      (node (ref "R2") (pin "2") (pinfunction "2_2") (pintype "passive"))
    )
    (net (code "44") (name "Net-(J3-SHLD-PadSHLD1)") (class "Default")
      (node (ref "J3") (pin "SHLD1") (pinfunction "SHLD_SHLD1") (pintype "bidirectional"))
      (node (ref "J3") (pin "SHLD2") (pinfunction "SHLD_SHLD2") (pintype "bidirectional"))
      (node (ref "J3") (pin "SHLD3") (pinfunction "SHLD_SHLD3") (pintype "bidirectional"))
      (node (ref "J3") (pin "SHLD4") (pinfunction "SHLD_SHLD4") (pintype "bidirectional"))
      (node (ref "SHLD") (pin "2") (pinfunction "2_2") (pintype "passive"))
    )
    (net (code "45") (name "Net-(U2-PROG)") (class "Default")
      (node (ref "R3") (pin "2") (pinfunction "2_2") (pintype "passive"))
      (node (ref "U2") (pin "5") (pinfunction "PROG_5") (pintype "input"))
    )
    (net (code "46") (name "Net-(U2-STAT)") (class "Default")
      (node (ref "R5") (pin "1") (pinfunction "1_1") (pintype "passive"))
      (node (ref "U2") (pin "1") (pinfunction "STAT_1") (pintype "output"))
    )
    (net (code "47") (name "Net-(U5-EN)") (class "Default")
      (node (ref "D1") (pin "C") (pinfunction "C_C") (pintype "passive"))
      (node (ref "R9") (pin "1") (pinfunction "1_1") (pintype "passive"))
      (node (ref "U5") (pin "5") (pinfunction "EN_5") (pintype "bidirectional"))
      (node (ref "VE") (pin "2") (pinfunction "2_2") (pintype "passive"))
    )
    (net (code "48") (name "Net-(U5-IN)") (class "Default")
      (node (ref "5V_MEAS") (pin "2") (pinfunction "2_2") (pintype "passive"))
      (node (ref "5V_MEAS") (pin "4") (pinfunction "2_4") (pintype "passive"))
      (node (ref "C5") (pin "1") (pinfunction "1_1") (pintype "passive"))
      (node (ref "C8") (pin "1") (pinfunction "1_1") (pintype "passive"))
      (node (ref "R9") (pin "2") (pinfunction "2_2") (pintype "passive"))
      (node (ref "U5") (pin "8") (pinfunction "IN_8") (pintype "input"))
    )
    (net (code "49") (name "Net-(U5-OUT)") (class "Default")
      (node (ref "3V3_MEAS") (pin "1") (pinfunction "1_1") (pintype "passive"))
      (node (ref "3V3_MEAS") (pin "3") (pinfunction "1_3") (pintype "passive"))
      (node (ref "C11") (pin "1") (pinfunction "1_1") (pintype "passive"))
      (node (ref "C9") (pin "1") (pinfunction "1_1") (pintype "passive"))
      (node (ref "U5") (pin "1") (pinfunction "OUT_1") (pintype "output"))
    )
    (net (code "50") (name "PROCESSOR_CAN-RX") (class "Default")
      (node (ref "J1") (pin "41") (pinfunction "CAN-RX_41") (pintype "bidirectional"))
      (node (ref "J6") (pin "43") (pinfunction "CAN-TX_43") (pintype "bidirectional"))
    )
    (net (code "51") (name "PROCESSOR_CAN-TX") (class "Default")
      (node (ref "J1") (pin "43") (pinfunction "CAN-TX_43") (pintype "bidirectional"))
      (node (ref "J6") (pin "41") (pinfunction "CAN-RX_41") (pintype "bidirectional"))
    )
    (net (code "52") (name "PWM0-PROCESSOR") (class "Default")
      (node (ref "J1") (pin "32") (pinfunction "PWM0_32") (pintype "bidirectional"))
      (node (ref "J6") (pin "51") (pinfunction "F2/PWM_51") (pintype "bidirectional"))
    )
    (net (code "53") (name "PWM1-PROCESSOR") (class "Default")
      (node (ref "J1") (pin "47") (pinfunction "PWM1_47") (pintype "bidirectional"))
      (node (ref "J7") (pin "51") (pinfunction "F2/PWM_51") (pintype "bidirectional"))
    )
    (net (code "54") (name "RTS1-PROCESSOR") (class "Default")
      (node (ref "J1") (pin "13") (pinfunction "RTS1_13") (pintype "bidirectional"))
      (node (ref "J6") (pin "18") (pinfunction "CTS_18") (pintype "bidirectional"))
    )
    (net (code "55") (name "RX1-DFU_TX-FC0-PLEX") (class "Default")
      (node (ref "J6") (pin "4") (pinfunction "MCU_DFU_TX_4") (pintype "bidirectional"))
    )
    (net (code "56") (name "RX1-DFU_TX-FC1-PLEX") (class "Default")
      (node (ref "J7") (pin "4") (pinfunction "MCU_DFU_TX_4") (pintype "bidirectional"))
    )
    (net (code "57") (name "RX1-PROCESSOR") (class "Default")
      (node (ref "J1") (pin "19") (pinfunction "RX1_19") (pintype "bidirectional"))
    )
    (net (code "58") (name "RX1-PROCESSOR-PLEX") (class "Default")
      (node (ref "J6") (pin "13") (pinfunction "TX_13") (pintype "bidirectional"))
    )
    (net (code "59") (name "RX2-PROCESSOR") (class "Default")
      (node (ref "J1") (pin "20") (pinfunction "RX2_20") (pintype "bidirectional"))
      (node (ref "J7") (pin "13") (pinfunction "TX_13") (pintype "bidirectional"))
    )
    (net (code "60") (name "SDIO_DATA1{slash}PWR_EN1_ALT") (class "Default")
      (node (ref "J1") (pin "66") (pinfunction "SDIO_DATA1_66") (pintype "bidirectional"))
      (node (ref "J7") (pin "71") (pinfunction "PWR_EN_71") (pintype "bidirectional"))
      (node (ref "S7") (pin "3") (pinfunction "S_3") (pintype "passive"))
    )
    (net (code "61") (name "SDIO_DATA2{slash}PWR_EN0_ALT") (class "Default")
      (node (ref "J1") (pin "68") (pinfunction "SDIO_DATA2_68") (pintype "bidirectional"))
      (node (ref "J6") (pin "71") (pinfunction "PWR_EN_71") (pintype "bidirectional"))
      (node (ref "S3") (pin "3") (pinfunction "S_3") (pintype "passive"))
    )
    (net (code "62") (name "SPI_PROCESSOR_SCK") (class "Default")
      (node (ref "J1") (pin "57") (pinfunction "SPI_SCK_57") (pintype "bidirectional"))
      (node (ref "J10") (pin "5") (pinfunction "CLK/SCK_5") (pintype "bidirectional"))
      (node (ref "J6") (pin "3") (pinfunction "SPI_SCK_3") (pintype "bidirectional"))
      (node (ref "J7") (pin "3") (pinfunction "SPI_SCK_3") (pintype "bidirectional"))
    )
    (net (code "63") (name "SPI_PROCESSOR_SDI") (class "Default")
      (node (ref "J1") (pin "61") (pinfunction "SPI_SDI_61") (pintype "bidirectional"))
      (node (ref "J10") (pin "7") (pinfunction "DAT0/SDO_7") (pintype "bidirectional"))
      (node (ref "J6") (pin "7") (pinfunction "SPI_SDO_7") (pintype "bidirectional"))
      (node (ref "J7") (pin "7") (pinfunction "SPI_SDO_7") (pintype "bidirectional"))
    )
    (net (code "64") (name "SPI_PROCESSOR_SDO") (class "Default")
      (node (ref "J1") (pin "59") (pinfunction "SPI_SDO_59") (pintype "bidirectional"))
      (node (ref "J10") (pin "3") (pinfunction "CMD/SDI_3") (pintype "bidirectional"))
      (node (ref "J6") (pin "5") (pinfunction "SPI_SDI_5") (pintype "bidirectional"))
      (node (ref "J7") (pin "5") (pinfunction "SPI_SDI_5") (pintype "bidirectional"))
    )
    (net (code "65") (name "SPI_SCK1-PROCESSOR") (class "Default")
      (node (ref "J1") (pin "60") (pinfunction "SPI_SCK1/SDIO_CLK_60") (pintype "bidirectional"))
      (node (ref "J7") (pin "61") (pinfunction "F7_61") (pintype "bidirectional"))
    )
    (net (code "66") (name "SPI_SDO1-PROCESSOR") (class "Default")
      (node (ref "J1") (pin "62") (pinfunction "SPI_SDO1/SDIO_CMD_62") (pintype "bidirectional"))
      (node (ref "J7") (pin "59") (pinfunction "F6_59") (pintype "bidirectional"))
    )
    (net (code "67") (name "SWDCK") (class "Default")
      (node (ref "J1") (pin "21") (pinfunction "SWDCK_21") (pintype "bidirectional"))
      (node (ref "J5") (pin "4") (pinfunction "SWDCLK_4") (pintype "bidirectional"))
    )
    (net (code "68") (name "SWDIO") (class "Default")
      (node (ref "J1") (pin "23") (pinfunction "SWDIO_23") (pintype "bidirectional"))
      (node (ref "J5") (pin "2") (pinfunction "SWDIO_2") (pintype "bidirectional"))
      (node (ref "TP1") (pin "1") (pinfunction "1_1") (pintype "bidirectional"))
    )
    (net (code "69") (name "TX1-DFU_RX-FC0-PLEX") (class "Default")
      (node (ref "J6") (pin "6") (pinfunction "MCU_DFU_RX_6") (pintype "bidirectional"))
    )
    (net (code "70") (name "TX1-DFU_RX-FC1-PLEX") (class "Default")
      (node (ref "J7") (pin "6") (pinfunction "MCU_DFU_RX_6") (pintype "bidirectional"))
    )
    (net (code "71") (name "TX1-PROCESSOR") (class "Default")
      (node (ref "J1") (pin "17") (pinfunction "TX1_17") (pintype "bidirectional"))
    )
    (net (code "72") (name "TX1-PROCESSOR-PLEX") (class "Default")
      (node (ref "J6") (pin "15") (pinfunction "RX_15") (pintype "bidirectional"))
    )
    (net (code "73") (name "TX2-PROCESSOR") (class "Default")
      (node (ref "J1") (pin "22") (pinfunction "TX2_22") (pintype "bidirectional"))
      (node (ref "J7") (pin "15") (pinfunction "RX_15") (pintype "bidirectional"))
    )
    (net (code "74") (name "VCC") (class "Default")
      (node (ref "5V_MEAS") (pin "1") (pinfunction "1_1") (pintype "passive"))
      (node (ref "5V_MEAS") (pin "3") (pinfunction "1_3") (pintype "passive"))
      (node (ref "C2") (pin "1") (pinfunction "1_1") (pintype "passive"))
      (node (ref "C3") (pin "1") (pinfunction "1_1") (pintype "passive"))
      (node (ref "D4") (pin "A") (pinfunction "A_A") (pintype "passive"))
      (node (ref "D5") (pin "C") (pinfunction "C_C") (pintype "passive"))
      (node (ref "J6") (pin "72") (pinfunction "VCC_72") (pintype "bidirectional"))
      (node (ref "J6") (pin "74") (pinfunction "VCC_74") (pintype "bidirectional"))
      (node (ref "J7") (pin "72") (pinfunction "VCC_72") (pintype "bidirectional"))
      (node (ref "J7") (pin "74") (pinfunction "VCC_74") (pintype "bidirectional"))
      (node (ref "Q1") (pin "2") (pinfunction "S_2") (pintype "bidirectional"))
      (node (ref "R4") (pin "2") (pinfunction "2_2") (pintype "passive"))
      (node (ref "U2") (pin "4") (pinfunction "VIN_4") (pintype "power_in"))
      (node (ref "U4") (pin "1") (pinfunction "IN_1") (pintype "input"))
    )
    (net (code "75") (name "VIN") (class "Default")
      (node (ref "BYP") (pin "2") (pinfunction "2_2") (pintype "passive"))
      (node (ref "D5") (pin "A") (pinfunction "A_A") (pintype "passive"))
      (node (ref "F2") (pin "2") (pinfunction "2_2") (pintype "bidirectional"))
      (node (ref "J1") (pin "9") (pinfunction "USB_VIN_9") (pintype "bidirectional"))
      (node (ref "Q1") (pin "1") (pinfunction "G_1") (pintype "bidirectional"))
      (node (ref "R10") (pin "2") (pinfunction "2_2") (pintype "passive"))
      (node (ref "R6") (pin "2") (pinfunction "2_2") (pintype "passive"))
      (node (ref "R8") (pin "2") (pinfunction "2_2") (pintype "passive"))
      (node (ref "TP4") (pin "1") (pinfunction "1_1") (pintype "bidirectional"))
    )
    (net (code "76") (name "VIN{slash}3") (class "Default")
      (node (ref "J1") (pin "49") (pinfunction "BATT_VIN/3_49") (pintype "bidirectional"))
      (node (ref "R10") (pin "1") (pinfunction "1_1") (pintype "passive"))
      (node (ref "R7") (pin "2") (pinfunction "2_2") (pintype "passive"))
    )
    (net (code "77") (name "V_BATT") (class "Default")
      (node (ref "C4") (pin "1") (pinfunction "1_1") (pintype "passive"))
      (node (ref "J8") (pin "2") (pinfunction "+_2") (pintype "bidirectional"))
      (node (ref "Q1") (pin "3") (pinfunction "D_3") (pintype "bidirectional"))
      (node (ref "TP3") (pin "1") (pinfunction "1_1") (pintype "bidirectional"))
      (node (ref "U2") (pin "3") (pinfunction "VBAT_3") (pintype "power_in"))
    )
    (net (code "78") (name "V_USB") (class "Default")
      (node (ref "BYP") (pin "1") (pinfunction "1_1") (pintype "passive"))
      (node (ref "F2") (pin "1") (pinfunction "1_1") (pintype "bidirectional"))
      (node (ref "J3") (pin "VBUS1") (pinfunction "VBUS_VBUS1") (pintype "bidirectional"))
      (node (ref "J3") (pin "VBUS2") (pinfunction "VBUS_VBUS2") (pintype "bidirectional"))
      (node (ref "U3") (pin "5") (pinfunction "VCC_5") (pintype "bidirectional"))
    )
    (net (code "79") (name "unconnected-(J1-AUD_BCLK-Pad50)") (class "Default")
      (node (ref "J1") (pin "50") (pinfunction "AUD_BCLK_50") (pintype "bidirectional"))
    )
    (net (code "80") (name "unconnected-(J1-AUD_IN{slash}CAM_PCLK-Pad54)") (class "Default")
      (node (ref "J1") (pin "54") (pinfunction "AUD_IN/CAM_PCLK_54") (pintype "bidirectional"))
    )
    (net (code "81") (name "unconnected-(J1-AUD_LRCLK-Pad52)") (class "Default")
      (node (ref "J1") (pin "52") (pinfunction "AUD_LRCLK_52") (pintype "bidirectional"))
    )
    (net (code "82") (name "unconnected-(J1-AUD_MCLK-Pad58)") (class "Default")
      (node (ref "J1") (pin "58") (pinfunction "AUD_MCLK_58") (pintype "bidirectional"))
    )
    (net (code "83") (name "unconnected-(J1-AUD_OUT{slash}CAM_MCLK-Pad56)") (class "Default")
      (node (ref "J1") (pin "56") (pinfunction "AUD_OUT/CAM_MCLK_56") (pintype "bidirectional"))
    )
    (net (code "84") (name "unconnected-(J1-G8-Pad67)") (class "Default")
      (node (ref "J1") (pin "67") (pinfunction "G8_67") (pintype "bidirectional"))
    )
    (net (code "85") (name "unconnected-(J1-G9{slash}ADC_D-{slash}CAM_HSYNC-Pad65)") (class "Default")
      (node (ref "J1") (pin "65") (pinfunction "G9/ADC_D-/CAM_HSYNC_65") (pintype "bidirectional"))
    )
    (net (code "86") (name "unconnected-(J1-G10{slash}ADC_D+{slash}CAM_VSYNC-Pad63)") (class "Default")
      (node (ref "J1") (pin "63") (pinfunction "G10/ADC_D+/CAM_VSYNC_63") (pintype "bidirectional"))
    )
    (net (code "87") (name "unconnected-(J1-G11-Pad8)") (class "Default")
      (node (ref "J1") (pin "8") (pinfunction "G11_8") (pintype "bidirectional"))
    )
    (net (code "88") (name "unconnected-(J1-I2C_SDA1-Pad51)") (class "Default")
      (node (ref "J1") (pin "51") (pinfunction "I2C_SDA1_51") (pintype "bidirectional"))
    )
    (net (code "89") (name "unconnected-(J1-RTC_3V-Pad72)") (class "Default")
      (node (ref "J1") (pin "72") (pinfunction "RTC_3V_72") (pintype "bidirectional"))
    )
    (net (code "90") (name "unconnected-(J1-SPI_SDI1{slash}SDIO_DATA0-Pad64)") (class "Default")
      (node (ref "J1") (pin "64") (pinfunction "SPI_SDI1/SDIO_DATA0_64") (pintype "bidirectional"))
    )
    (net (code "91") (name "unconnected-(J5-SWO-Pad6)") (class "Default")
      (node (ref "J5") (pin "6") (pinfunction "SWO_6") (pintype "bidirectional"))
    )
    (net (code "92") (name "unconnected-(J6-EEPROM_WP-Pad40)") (class "Default")
      (node (ref "J6") (pin "40") (pinfunction "EEPROM_WP_40") (pintype "bidirectional"))
    )
    (net (code "93") (name "unconnected-(J6-USB_VIN-Pad70)") (class "Default")
      (node (ref "J6") (pin "70") (pinfunction "USB_VIN_70") (pintype "bidirectional"))
    )
    (net (code "94") (name "unconnected-(J7-CAN-RX-Pad41)") (class "Default")
      (node (ref "J7") (pin "41") (pinfunction "CAN-RX_41") (pintype "bidirectional"))
    )
    (net (code "95") (name "unconnected-(J7-CAN-TX-Pad43)") (class "Default")
      (node (ref "J7") (pin "43") (pinfunction "CAN-TX_43") (pintype "bidirectional"))
    )
    (net (code "96") (name "unconnected-(J7-CTS-Pad18)") (class "Default")
      (node (ref "J7") (pin "18") (pinfunction "CTS_18") (pintype "bidirectional"))
    )
    (net (code "97") (name "unconnected-(J7-EEPROM_WP-Pad40)") (class "Default")
      (node (ref "J7") (pin "40") (pinfunction "EEPROM_WP_40") (pintype "bidirectional"))
    )
    (net (code "98") (name "unconnected-(J7-RTS-Pad16)") (class "Default")
      (node (ref "J7") (pin "16") (pinfunction "RTS_16") (pintype "bidirectional"))
    )
    (net (code "99") (name "unconnected-(J7-USBHOST_D+-Pad35)") (class "Default")
      (node (ref "J7") (pin "35") (pinfunction "USBHOST_D+_35") (pintype "bidirectional"))
    )
    (net (code "100") (name "unconnected-(J7-USBHOST_D--Pad37)") (class "Default")
      (node (ref "J7") (pin "37") (pinfunction "USBHOST_D-_37") (pintype "bidirectional"))
    )
    (net (code "101") (name "unconnected-(J7-USB_VIN-Pad70)") (class "Default")
      (node (ref "J7") (pin "70") (pinfunction "USB_VIN_70") (pintype "bidirectional"))
    )
    (net (code "102") (name "unconnected-(J8-PAD1-PadNC1)") (class "Default")
      (node (ref "J8") (pin "NC1") (pinfunction "PAD1_NC1") (pintype "bidirectional"))
    )
    (net (code "103") (name "unconnected-(J8-PAD2-PadNC2)") (class "Default")
      (node (ref "J8") (pin "NC2") (pinfunction "PAD2_NC2") (pintype "bidirectional"))
    )
    (net (code "104") (name "unconnected-(J10-DAT1-Pad8)") (class "Default")
      (node (ref "J10") (pin "8") (pinfunction "DAT1_8") (pintype "bidirectional"))
    )
    (net (code "105") (name "unconnected-(J10-DAT2-Pad1)") (class "Default")
      (node (ref "J10") (pin "1") (pinfunction "DAT2_1") (pintype "bidirectional"))
    )
    (net (code "106") (name "unconnected-(J10-DET-Pad9)") (class "Default")
      (node (ref "J10") (pin "9") (pinfunction "DET_9") (pintype "bidirectional"))
    )
    (net (code "107") (name "unconnected-(U1-1A-PadP1)") (class "Default")
      (node (ref "U1") (pin "P1") (pinfunction "1A_P1") (pintype "bidirectional"))
    )
    (net (code "108") (name "unconnected-(U1-1B-PadP2)") (class "Default")
      (node (ref "U1") (pin "P2") (pinfunction "1B_P2") (pintype "bidirectional"))
    )
    (net (code "109") (name "unconnected-(U1-1C-PadP13)") (class "Default")
      (node (ref "U1") (pin "P13") (pinfunction "1C_P13") (pintype "bidirectional"))
    )
    (net (code "110") (name "unconnected-(U1-1Y-PadP12)") (class "Default")
      (node (ref "U1") (pin "P12") (pinfunction "1Y_P12") (pintype "bidirectional"))
    )
    (net (code "111") (name "unconnected-(U1-2A-PadP3)") (class "Default")
      (node (ref "U1") (pin "P3") (pinfunction "2A_P3") (pintype "bidirectional"))
    )
    (net (code "112") (name "unconnected-(U1-2B-PadP4)") (class "Default")
      (node (ref "U1") (pin "P4") (pinfunction "2B_P4") (pintype "bidirectional"))
    )
    (net (code "113") (name "unconnected-(U1-2C-PadP5)") (class "Default")
      (node (ref "U1") (pin "P5") (pinfunction "2C_P5") (pintype "bidirectional"))
    )
    (net (code "114") (name "unconnected-(U1-2Y-PadP6)") (class "Default")
      (node (ref "U1") (pin "P6") (pinfunction "2Y_P6") (pintype "bidirectional"))
    )
    (net (code "115") (name "unconnected-(U1-3A-PadP9)") (class "Default")
      (node (ref "U1") (pin "P9") (pinfunction "3A_P9") (pintype "bidirectional"))
    )
    (net (code "116") (name "unconnected-(U1-3B-PadP10)") (class "Default")
      (node (ref "U1") (pin "P10") (pinfunction "3B_P10") (pintype "bidirectional"))
    )
    (net (code "117") (name "unconnected-(U1-3C-PadP11)") (class "Default")
      (node (ref "U1") (pin "P11") (pinfunction "3C_P11") (pintype "bidirectional"))
    )
    (net (code "118") (name "unconnected-(U1-3Y-PadP8)") (class "Default")
      (node (ref "U1") (pin "P8") (pinfunction "3Y_P8") (pintype "bidirectional"))
    )
    (net (code "119") (name "unconnected-(U3-IO3-Pad4)") (class "Default")
      (node (ref "U3") (pin "4") (pinfunction "IO3_4") (pintype "bidirectional"))
    )
    (net (code "120") (name "unconnected-(U3-IO4-Pad6)") (class "Default")
      (node (ref "U3") (pin "6") (pinfunction "IO4_6") (pintype "bidirectional"))
    )
    (net (code "121") (name "unconnected-(U6-1A-PadP1)") (class "Default")
      (node (ref "U6") (pin "P1") (pinfunction "1A_P1") (pintype "input"))
    )
    (net (code "122") (name "unconnected-(U6-1Y-PadP4)") (class "Default")
      (node (ref "U6") (pin "P4") (pinfunction "1Y_P4") (pintype "output"))
    )
    (net (code "123") (name "unconnected-(U6-2A-PadP3)") (class "Default")
      (node (ref "U6") (pin "P3") (pinfunction "2A_P3") (pintype "input"))
    )
    (net (code "124") (name "unconnected-(U6-2Y-PadP6)") (class "Default")
      (node (ref "U6") (pin "P6") (pinfunction "2Y_P6") (pintype "output"))
    )
    (net (code "125") (name "unconnected-(U7-1A-PadP1)") (class "Default")
      (node (ref "U7") (pin "P1") (pinfunction "1A_P1") (pintype "bidirectional"))
    )
    (net (code "126") (name "unconnected-(U7-1B-PadP2)") (class "Default")
      (node (ref "U7") (pin "P2") (pinfunction "1B_P2") (pintype "bidirectional"))
    )
    (net (code "127") (name "unconnected-(U7-1C-PadP13)") (class "Default")
      (node (ref "U7") (pin "P13") (pinfunction "1C_P13") (pintype "bidirectional"))
    )
    (net (code "128") (name "unconnected-(U7-1Y-PadP12)") (class "Default")
      (node (ref "U7") (pin "P12") (pinfunction "1Y_P12") (pintype "bidirectional"))
    )
    (net (code "129") (name "unconnected-(U7-2A-PadP3)") (class "Default")
      (node (ref "U7") (pin "P3") (pinfunction "2A_P3") (pintype "bidirectional"))
    )
    (net (code "130") (name "unconnected-(U7-2B-PadP4)") (class "Default")
      (node (ref "U7") (pin "P4") (pinfunction "2B_P4") (pintype "bidirectional"))
    )
    (net (code "131") (name "unconnected-(U7-2C-PadP5)") (class "Default")
      (node (ref "U7") (pin "P5") (pinfunction "2C_P5") (pintype "bidirectional"))
    )
    (net (code "132") (name "unconnected-(U7-2Y-PadP6)") (class "Default")
      (node (ref "U7") (pin "P6") (pinfunction "2Y_P6") (pintype "bidirectional"))
    )
    (net (code "133") (name "unconnected-(U7-3A-PadP9)") (class "Default")
      (node (ref "U7") (pin "P9") (pinfunction "3A_P9") (pintype "bidirectional"))
    )
    (net (code "134") (name "unconnected-(U7-3B-PadP10)") (class "Default")
      (node (ref "U7") (pin "P10") (pinfunction "3B_P10") (pintype "bidirectional"))
    )
    (net (code "135") (name "unconnected-(U7-3C-PadP11)") (class "Default")
      (node (ref "U7") (pin "P11") (pinfunction "3C_P11") (pintype "bidirectional"))
    )
    (net (code "136") (name "unconnected-(U7-3Y-PadP8)") (class "Default")
      (node (ref "U7") (pin "P8") (pinfunction "3Y_P8") (pintype "bidirectional"))
    )
    (net (code "137") (name "unconnected-(U8-1A-PadP3)") (class "Default")
      (node (ref "U8") (pin "P3") (pinfunction "1A_P3") (pintype "bidirectional"))
    )
    (net (code "138") (name "unconnected-(U8-1B-PadP4)") (class "Default")
      (node (ref "U8") (pin "P4") (pinfunction "1B_P4") (pintype "bidirectional"))
    )
    (net (code "139") (name "unconnected-(U8-1C-PadP5)") (class "Default")
      (node (ref "U8") (pin "P5") (pinfunction "1C_P5") (pintype "bidirectional"))
    )
    (net (code "140") (name "unconnected-(U8-1Y-PadP6)") (class "Default")
      (node (ref "U8") (pin "P6") (pinfunction "1Y_P6") (pintype "bidirectional"))
    )
    (net (code "141") (name "unconnected-(U8-2A-PadP1)") (class "Default")
      (node (ref "U8") (pin "P1") (pinfunction "2A_P1") (pintype "bidirectional"))
    )
    (net (code "142") (name "unconnected-(U8-2B-PadP2)") (class "Default")
      (node (ref "U8") (pin "P2") (pinfunction "2B_P2") (pintype "bidirectional"))
    )
    (net (code "143") (name "unconnected-(U8-2C-PadP8)") (class "Default")
      (node (ref "U8") (pin "P8") (pinfunction "2C_P8") (pintype "bidirectional"))
    )
    (net (code "144") (name "unconnected-(U8-2Y-PadP9)") (class "Default")
      (node (ref "U8") (pin "P9") (pinfunction "2Y_P9") (pintype "bidirectional"))
    )
    (net (code "145") (name "unconnected-(U8-3A-PadP11)") (class "Default")
      (node (ref "U8") (pin "P11") (pinfunction "3A_P11") (pintype "bidirectional"))
    )
    (net (code "146") (name "unconnected-(U8-3B-PadP12)") (class "Default")
      (node (ref "U8") (pin "P12") (pinfunction "3B_P12") (pintype "bidirectional"))
    )
    (net (code "147") (name "unconnected-(U8-3C-PadP13)") (class "Default")
      (node (ref "U8") (pin "P13") (pinfunction "3C_P13") (pintype "bidirectional"))
    )
    (net (code "148") (name "unconnected-(U8-3Y-PadP10)") (class "Default")
      (node (ref "U8") (pin "P10") (pinfunction "3Y_P10") (pintype "bidirectional"))
    )
  )
)
